# Qwiic_MultiStar.net
KiCad netlist of a schematic drawn in EAGLE
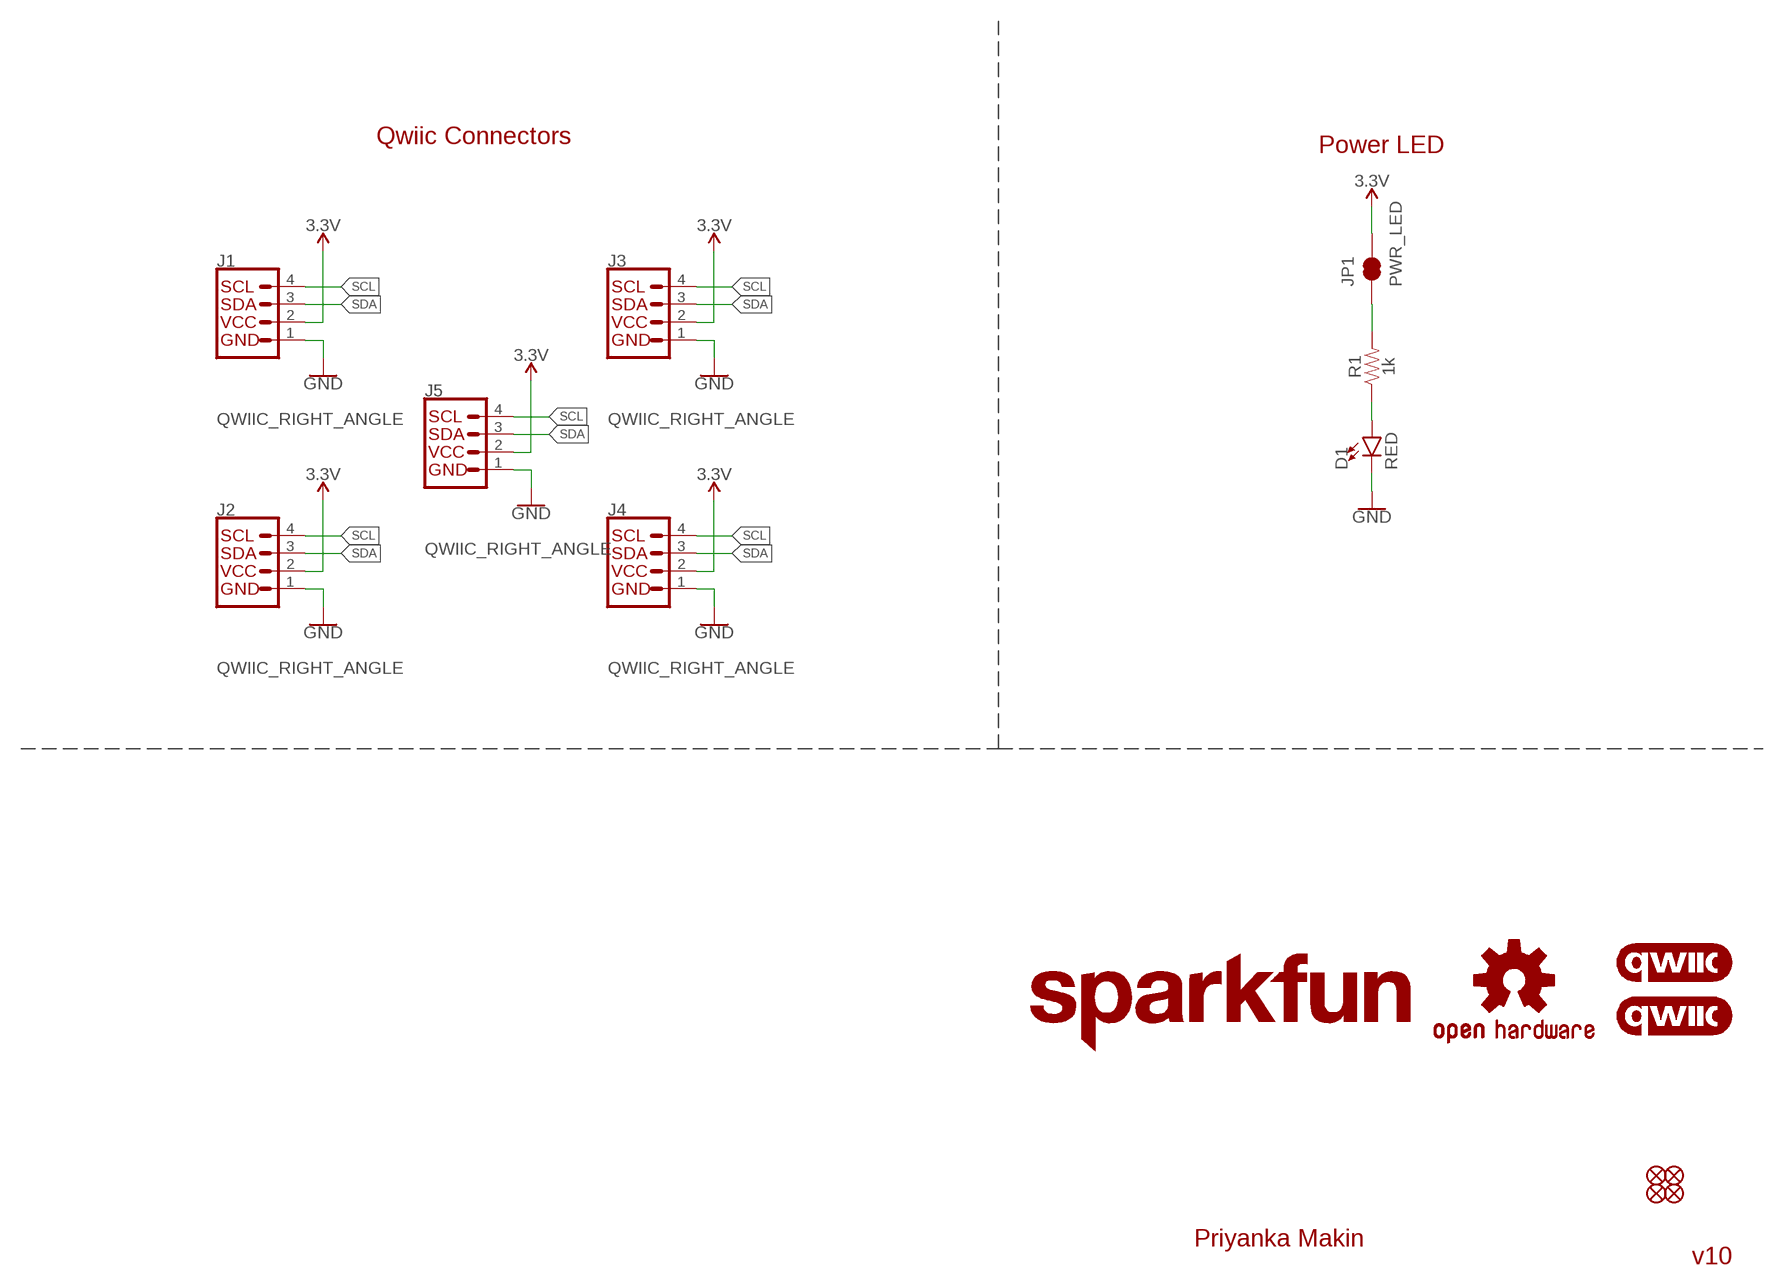
[diagram p0: schematic, sheet 1]

(export (version "E")
  (design (tool "Eeschema 10.0.6"))
  (components
    (comp (ref "D1")
      (value "RED")
      (footprint "eagle-import:LED-0603")
      (libsource (lib "eagle-import") (part "LED-RED0603"))
    )
    (comp (ref "FD1")
      (value "FIDUCIAL1X2")
      (footprint "eagle-import:FIDUCIAL-1X2")
      (libsource (lib "eagle-import") (part "FIDUCIAL1X2"))
    )
    (comp (ref "FD2")
      (value "FIDUCIAL1X2")
      (footprint "eagle-import:FIDUCIAL-1X2")
      (libsource (lib "eagle-import") (part "FIDUCIAL1X2"))
    )
    (comp (ref "FD3")
      (value "FIDUCIAL1X2")
      (footprint "eagle-import:FIDUCIAL-1X2")
      (libsource (lib "eagle-import") (part "FIDUCIAL1X2"))
    )
    (comp (ref "FD4")
      (value "FIDUCIAL1X2")
      (footprint "eagle-import:FIDUCIAL-1X2")
      (libsource (lib "eagle-import") (part "FIDUCIAL1X2"))
    )
    (comp (ref "J1")
      (value "QWIIC_RIGHT_ANGLE")
      (footprint "eagle-import:JST04_1MM_RA")
      (libsource (lib "eagle-import") (part "QWIIC_CONNECTORJS-1MM"))
    )
    (comp (ref "J2")
      (value "QWIIC_RIGHT_ANGLE")
      (footprint "eagle-import:JST04_1MM_RA")
      (libsource (lib "eagle-import") (part "QWIIC_CONNECTORJS-1MM"))
    )
    (comp (ref "J3")
      (value "QWIIC_RIGHT_ANGLE")
      (footprint "eagle-import:JST04_1MM_RA")
      (libsource (lib "eagle-import") (part "QWIIC_CONNECTORJS-1MM"))
    )
    (comp (ref "J4")
      (value "QWIIC_RIGHT_ANGLE")
      (footprint "eagle-import:JST04_1MM_RA")
      (libsource (lib "eagle-import") (part "QWIIC_CONNECTORJS-1MM"))
    )
    (comp (ref "J5")
      (value "QWIIC_RIGHT_ANGLE")
      (footprint "eagle-import:JST04_1MM_RA")
      (libsource (lib "eagle-import") (part "QWIIC_CONNECTORJS-1MM"))
    )
    (comp (ref "JP1")
      (value "PWR_LED")
      (footprint "eagle-import:SMT-JUMPER_2_NC_TRACE_SILK")
      (libsource (lib "eagle-import") (part "JUMPER-SMT_2_NC_TRACE_SILK"))
    )
    (comp (ref "LOGO1")
      (value "QWIIC_LOGO_5MM")
      (footprint "eagle-import:QWIIC_5MM")
      (libsource (lib "eagle-import") (part "QWIIC_LOGO_5MM"))
    )
    (comp (ref "LOGO2")
      (value "QWIIC_LOGO_5MM")
      (footprint "eagle-import:QWIIC_5MM")
      (libsource (lib "eagle-import") (part "QWIIC_LOGO_5MM"))
    )
    (comp (ref "LOGO3")
      (value "OSHW-LOGOS")
      (footprint "eagle-import:OSHW-LOGO-S")
      (libsource (lib "eagle-import") (part "OSHW-LOGOS"))
    )
    (comp (ref "LOGO4")
      (value "SFE_LOGO_NAME.2_INCH")
      (footprint "eagle-import:SFE_LOGO_NAME_.2")
      (libsource (lib "eagle-import") (part "SFE_LOGO_NAME.2_INCH"))
    )
    (comp (ref "R1")
      (value "1k")
      (footprint "eagle-import:0603")
      (libsource (lib "eagle-import") (part "1KOHM-0603-1/10W-1%"))
    )
  )
  (nets
    (net (code "1") (name "3.3V") (class "Default")
      (node (ref "J1") (pin "2") (pinfunction "2_2") (pintype "power_in"))
      (node (ref "J2") (pin "2") (pinfunction "2_2") (pintype "power_in"))
      (node (ref "J3") (pin "2") (pinfunction "2_2") (pintype "power_in"))
      (node (ref "J4") (pin "2") (pinfunction "2_2") (pintype "power_in"))
      (node (ref "J5") (pin "2") (pinfunction "2_2") (pintype "power_in"))
      (node (ref "JP1") (pin "2") (pinfunction "2_2") (pintype "passive"))
    )
    (net (code "2") (name "GND") (class "Default")
      (node (ref "D1") (pin "C") (pinfunction "C_C") (pintype "passive"))
      (node (ref "J1") (pin "1") (pinfunction "1_1") (pintype "power_in"))
      (node (ref "J2") (pin "1") (pinfunction "1_1") (pintype "power_in"))
      (node (ref "J3") (pin "1") (pinfunction "1_1") (pintype "power_in"))
      (node (ref "J4") (pin "1") (pinfunction "1_1") (pintype "power_in"))
      (node (ref "J5") (pin "1") (pinfunction "1_1") (pintype "power_in"))
    )
    (net (code "3") (name "Net-(D1-PadA)") (class "Default")
      (node (ref "D1") (pin "A") (pinfunction "A_A") (pintype "passive"))
      (node (ref "R1") (pin "1") (pinfunction "1_1") (pintype "passive"))
    )
    (net (code "4") (name "Net-(JP1-Pad1)") (class "Default")
      (node (ref "JP1") (pin "1") (pinfunction "1_1") (pintype "passive"))
      (node (ref "R1") (pin "2") (pinfunction "2_2") (pintype "passive"))
    )
    (net (code "5") (name "SCL") (class "Default")
      (node (ref "J1") (pin "4") (pinfunction "4_4") (pintype "passive"))
      (node (ref "J2") (pin "4") (pinfunction "4_4") (pintype "passive"))
      (node (ref "J3") (pin "4") (pinfunction "4_4") (pintype "passive"))
      (node (ref "J4") (pin "4") (pinfunction "4_4") (pintype "passive"))
      (node (ref "J5") (pin "4") (pinfunction "4_4") (pintype "passive"))
    )
    (net (code "6") (name "SDA") (class "Default")
      (node (ref "J1") (pin "3") (pinfunction "3_3") (pintype "passive"))
      (node (ref "J2") (pin "3") (pinfunction "3_3") (pintype "passive"))
      (node (ref "J3") (pin "3") (pinfunction "3_3") (pintype "passive"))
      (node (ref "J4") (pin "3") (pinfunction "3_3") (pintype "passive"))
      (node (ref "J5") (pin "3") (pinfunction "3_3") (pintype "passive"))
    )
  )
)
